# wheelBoardStock.net
KiCad netlist of a schematic drawn in EAGLE
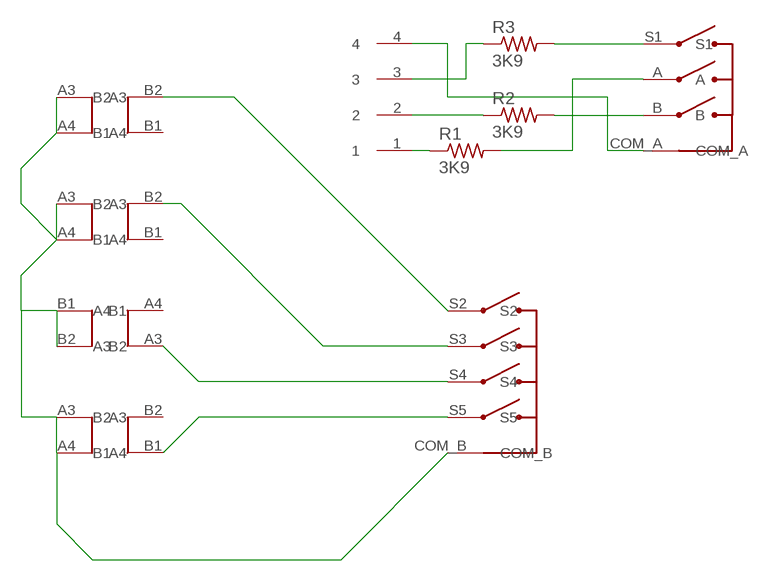
[diagram p0: schematic, sheet 1]

(export (version "E")
  (design (tool "Eeschema 10.0.6"))
  (components
    (comp (ref "R1")
      (value "3K9")
      (footprint "eagle-import:R1206")
      (libsource (lib "eagle-import") (part "R-US_R1206"))
    )
    (comp (ref "R2")
      (value "3K9")
      (footprint "eagle-import:R1206")
      (libsource (lib "eagle-import") (part "R-US_R1206"))
    )
    (comp (ref "R3")
      (value "3K9")
      (footprint "eagle-import:R1206")
      (libsource (lib "eagle-import") (part "R-US_R1206"))
    )
    (comp (ref "U$1")
      (value "TSWB-3N-CB222")
      (footprint "eagle-import:W_DIREC")
      (libsource (lib "eagle-import") (part "TSWB-3N-CB222"))
    )
    (comp (ref "U$2")
      (value "9X_TACT_PATCH")
      (footprint "eagle-import:9XTACTPADS")
      (libsource (lib "eagle-import") (part "9X_TACT_PATCH"))
    )
    (comp (ref "U$3")
      (value "9X_TACT_PATCH")
      (footprint "eagle-import:9XTACTPADS")
      (libsource (lib "eagle-import") (part "9X_TACT_PATCH"))
    )
    (comp (ref "U$4")
      (value "9X_TACT_PATCH")
      (footprint "eagle-import:9XTACTPADS")
      (libsource (lib "eagle-import") (part "9X_TACT_PATCH"))
    )
    (comp (ref "U$5")
      (value "9X_TACT_PATCH")
      (footprint "eagle-import:9XTACTPADS")
      (libsource (lib "eagle-import") (part "9X_TACT_PATCH"))
    )
    (comp (ref "U$6")
      (value "2MM_4P_HEADER")
      (footprint "eagle-import:JST2MM_4P")
      (libsource (lib "eagle-import") (part "2MM_4P_HEADER"))
    )
  )
  (nets
    (net (code "1") (name "Net-(R1-Pad1)") (class "Default")
      (node (ref "R1") (pin "1") (pinfunction "1_1") (pintype "passive"))
      (node (ref "U$6") (pin "1") (pinfunction "1_1") (pintype "bidirectional"))
    )
    (net (code "2") (name "Net-(R1-Pad2)") (class "Default")
      (node (ref "R1") (pin "2") (pinfunction "2_2") (pintype "passive"))
      (node (ref "U$1") (pin "A") (pinfunction "A_A") (pintype "bidirectional"))
    )
    (net (code "3") (name "Net-(R2-Pad1)") (class "Default")
      (node (ref "R2") (pin "1") (pinfunction "1_1") (pintype "passive"))
      (node (ref "U$6") (pin "2") (pinfunction "2_2") (pintype "bidirectional"))
    )
    (net (code "4") (name "Net-(R2-Pad2)") (class "Default")
      (node (ref "R2") (pin "2") (pinfunction "2_2") (pintype "passive"))
      (node (ref "U$1") (pin "B") (pinfunction "B_B") (pintype "bidirectional"))
    )
    (net (code "5") (name "Net-(R3-Pad1)") (class "Default")
      (node (ref "R3") (pin "1") (pinfunction "1_1") (pintype "passive"))
      (node (ref "U$6") (pin "3") (pinfunction "3_3") (pintype "bidirectional"))
    )
    (net (code "6") (name "Net-(R3-Pad2)") (class "Default")
      (node (ref "R3") (pin "2") (pinfunction "2_2") (pintype "passive"))
      (node (ref "U$1") (pin "S1") (pinfunction "S1_S1") (pintype "bidirectional"))
    )
    (net (code "7") (name "Net-(U$1-PadCOM_A)") (class "Default")
      (node (ref "U$1") (pin "COM_A") (pinfunction "COM_A_COM_A") (pintype "bidirectional"))
      (node (ref "U$6") (pin "4") (pinfunction "4_4") (pintype "bidirectional"))
    )
    (net (code "8") (name "Net-(U$1-PadCOM_B)") (class "Default")
      (node (ref "U$1") (pin "COM_B") (pinfunction "COM_B_COM_B") (pintype "bidirectional"))
      (node (ref "U$2") (pin "A3") (pinfunction "A3_A3") (pintype "bidirectional"))
      (node (ref "U$2") (pin "A4") (pinfunction "A4_A4") (pintype "bidirectional"))
      (node (ref "U$3") (pin "A3") (pinfunction "A3_A3") (pintype "bidirectional"))
      (node (ref "U$3") (pin "A4") (pinfunction "A4_A4") (pintype "bidirectional"))
      (node (ref "U$4") (pin "B1") (pinfunction "B1_B1") (pintype "bidirectional"))
      (node (ref "U$4") (pin "B2") (pinfunction "B2_B2") (pintype "bidirectional"))
      (node (ref "U$5") (pin "A3") (pinfunction "A3_A3") (pintype "bidirectional"))
      (node (ref "U$5") (pin "A4") (pinfunction "A4_A4") (pintype "bidirectional"))
    )
    (net (code "9") (name "Net-(U$1-PadS2)") (class "Default")
      (node (ref "U$1") (pin "S2") (pinfunction "S2_S2") (pintype "bidirectional"))
      (node (ref "U$2") (pin "B2") (pinfunction "B2_B2") (pintype "bidirectional"))
    )
    (net (code "10") (name "Net-(U$1-PadS3)") (class "Default")
      (node (ref "U$1") (pin "S3") (pinfunction "S3_S3") (pintype "bidirectional"))
      (node (ref "U$3") (pin "B2") (pinfunction "B2_B2") (pintype "bidirectional"))
    )
    (net (code "11") (name "Net-(U$1-PadS4)") (class "Default")
      (node (ref "U$1") (pin "S4") (pinfunction "S4_S4") (pintype "bidirectional"))
      (node (ref "U$4") (pin "A3") (pinfunction "A3_A3") (pintype "bidirectional"))
    )
    (net (code "12") (name "Net-(U$1-PadS5)") (class "Default")
      (node (ref "U$1") (pin "S5") (pinfunction "S5_S5") (pintype "bidirectional"))
      (node (ref "U$5") (pin "B1") (pinfunction "B1_B1") (pintype "bidirectional"))
    )
    (net (code "13") (name "unconnected-(U$2-PadB1)") (class "Default")
      (node (ref "U$2") (pin "B1") (pinfunction "B1_B1") (pintype "bidirectional"))
    )
    (net (code "14") (name "unconnected-(U$3-PadB1)") (class "Default")
      (node (ref "U$3") (pin "B1") (pinfunction "B1_B1") (pintype "bidirectional"))
    )
    (net (code "15") (name "unconnected-(U$4-PadA4)") (class "Default")
      (node (ref "U$4") (pin "A4") (pinfunction "A4_A4") (pintype "bidirectional"))
    )
    (net (code "16") (name "unconnected-(U$5-PadB2)") (class "Default")
      (node (ref "U$5") (pin "B2") (pinfunction "B2_B2") (pintype "bidirectional"))
    )
  )
)
